# bridge_bq79600.net
KiCad netlist of a schematic drawn in Altium Designer
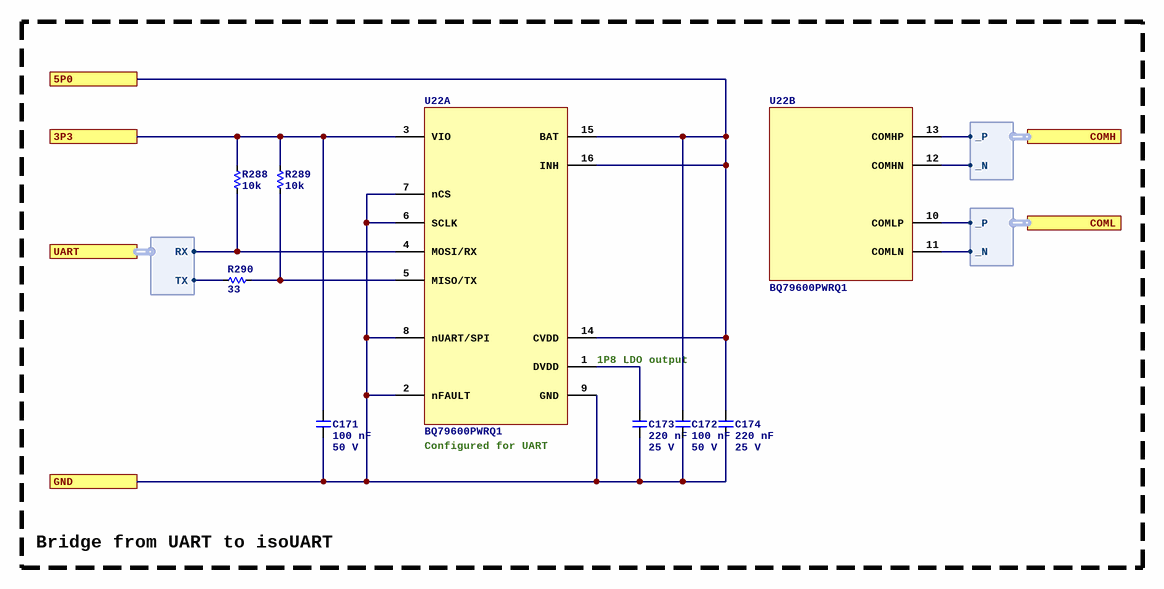
[diagram p0: bridge_bq79600.SchDoc]

(export (version "E")
  (design (tool "Eeschema 10.0.6"))
  (components
    (comp (ref "C171")
      (value "CL05B104KB54PNC")
      (footprint "C0402")
      (fields
        (field (name "CAPACITANCE") "100 nF")
        (field (name "MANUFACTURER") "Samsung Electro-Mechanics")
        (field (name "VOLTAGE RATING") "50 V")
      )
      (libsource (lib "database") (part "__template_cap"))
    )
    (comp (ref "C172")
      (value "CL05B104KB54PNC")
      (footprint "C0402")
      (fields
        (field (name "CAPACITANCE") "100 nF")
        (field (name "MANUFACTURER") "Samsung Electro-Mechanics")
        (field (name "VOLTAGE RATING") "50 V")
      )
      (libsource (lib "database") (part "__template_cap"))
    )
    (comp (ref "C173")
      (value "TMK105B7224KV-FR")
      (footprint "C0402")
      (fields
        (field (name "CAPACITANCE") "220 nF")
        (field (name "MANUFACTURER") "Taiyo Yuden")
        (field (name "VOLTAGE RATING") "25 V")
      )
      (libsource (lib "database") (part "__template_cap"))
    )
    (comp (ref "C174")
      (value "TMK105B7224KV-FR")
      (footprint "C0402")
      (fields
        (field (name "CAPACITANCE") "220 nF")
        (field (name "MANUFACTURER") "Taiyo Yuden")
        (field (name "VOLTAGE RATING") "25 V")
      )
      (libsource (lib "database") (part "__template_cap"))
    )
    (comp (ref "R288")
      (value "10k")
      (footprint "R0402")
      (fields
        (field (name "TOLERANCE") "1%")
        (field (name "MANUFACTURER PART NUMBER") "0402WGF1002TCE")
        (field (name "MANUFACTURER") "UNI-ROYAL(Uniroyal Elec)")
      )
      (libsource (lib "database") (part "__template_resistor"))
    )
    (comp (ref "R289")
      (value "10k")
      (footprint "R0402")
      (fields
        (field (name "TOLERANCE") "1%")
        (field (name "MANUFACTURER PART NUMBER") "0402WGF1002TCE")
        (field (name "MANUFACTURER") "UNI-ROYAL(Uniroyal Elec)")
      )
      (libsource (lib "database") (part "__template_resistor"))
    )
    (comp (ref "R290")
      (value "33")
      (footprint "R0402")
      (fields
        (field (name "TOLERANCE") "1%")
        (field (name "MANUFACTURER PART NUMBER") "0402WGF330JTCE")
        (field (name "MANUFACTURER") "UNI-ROYAL(Uniroyal Elec)")
      )
      (libsource (lib "database") (part "__template_resistor"))
    )
    (comp (ref "U22")
      (value "BQ79600PWRQ1")
      (footprint "TI_PW0016A")
      (description "Automotive SPI/UART communication interface functional-safety compliant with automatic host wakeup")
      (fields (field (name "MANUFACTURER") "Texas Instruments"))
      (libsource (lib "database") (part "BQ79600PWRQ1"))
    )
  )
  (nets
    (net (code "3") (name "/3P3") (class "Default")
      (node (ref "C171") (pin "1") (pintype "passive"))
      (node (ref "R288") (pin "2") (pintype "passive"))
      (node (ref "R289") (pin "2") (pintype "passive"))
      (node (ref "U22") (pin "3") (pinfunction "VIO_3") (pintype "passive"))
    )
    (net (code "4") (name "/5P0") (class "Default")
      (node (ref "C172") (pin "1") (pintype "passive"))
      (node (ref "C174") (pin "1") (pintype "passive"))
      (node (ref "U22") (pin "14") (pinfunction "CVDD_14") (pintype "passive"))
      (node (ref "U22") (pin "15") (pinfunction "BAT_15") (pintype "passive"))
      (node (ref "U22") (pin "16") (pinfunction "INH_16") (pintype "passive"))
    )
    (net (code "5") (name "/GND") (class "Default")
      (node (ref "C171") (pin "2") (pintype "passive"))
      (node (ref "C172") (pin "2") (pintype "passive"))
      (node (ref "C173") (pin "2") (pintype "passive"))
      (node (ref "C174") (pin "2") (pintype "passive"))
      (node (ref "U22") (pin "2") (pinfunction "nFAULT_2") (pintype "passive"))
      (node (ref "U22") (pin "6") (pinfunction "SCLK_6") (pintype "passive"))
      (node (ref "U22") (pin "7") (pinfunction "nCS_7") (pintype "passive"))
      (node (ref "U22") (pin "8") (pinfunction "nUART/SPI_8") (pintype "passive"))
      (node (ref "U22") (pin "9") (pinfunction "GND_9") (pintype "passive"))
    )
    (net (code "6") (name "/RX") (class "Default")
      (node (ref "R288") (pin "1") (pintype "passive"))
      (node (ref "U22") (pin "4") (pinfunction "MOSI/RX_4") (pintype "passive"))
    )
    (net (code "7") (name "/TX") (class "Default") (node (ref "R290") (pin "2") (pintype "passive")))
    (net (code "10") (name "Net-(U22A-DVDD)") (class "Default")
      (node (ref "C173") (pin "1") (pintype "passive"))
      (node (ref "U22") (pin "1") (pinfunction "DVDD_1") (pintype "passive"))
    )
    (net (code "11") (name "Net-(U22A-MISO{slash}TX)") (class "Default")
      (node (ref "R289") (pin "1") (pintype "passive"))
      (node (ref "R290") (pin "1") (pintype "passive"))
      (node (ref "U22") (pin "5") (pinfunction "MISO/TX_5") (pintype "passive"))
    )
    (net (code "12") (name "unconnected-(U22B-COMHN-Pad12)") (class "Default")
      (node (ref "U22") (pin "12") (pinfunction "COMHN_12") (pintype "passive"))
    )
    (net (code "13") (name "unconnected-(U22B-COMHP-Pad13)") (class "Default")
      (node (ref "U22") (pin "13") (pinfunction "COMHP_13") (pintype "passive"))
    )
    (net (code "14") (name "unconnected-(U22B-COMLN-Pad11)") (class "Default")
      (node (ref "U22") (pin "11") (pinfunction "COMLN_11") (pintype "passive"))
    )
    (net (code "15") (name "unconnected-(U22B-COMLP-Pad10)") (class "Default")
      (node (ref "U22") (pin "10") (pinfunction "COMLP_10") (pintype "passive"))
    )
  )
)
